# PWM-Power.net
KiCad netlist of a schematic drawn in Altium Designer
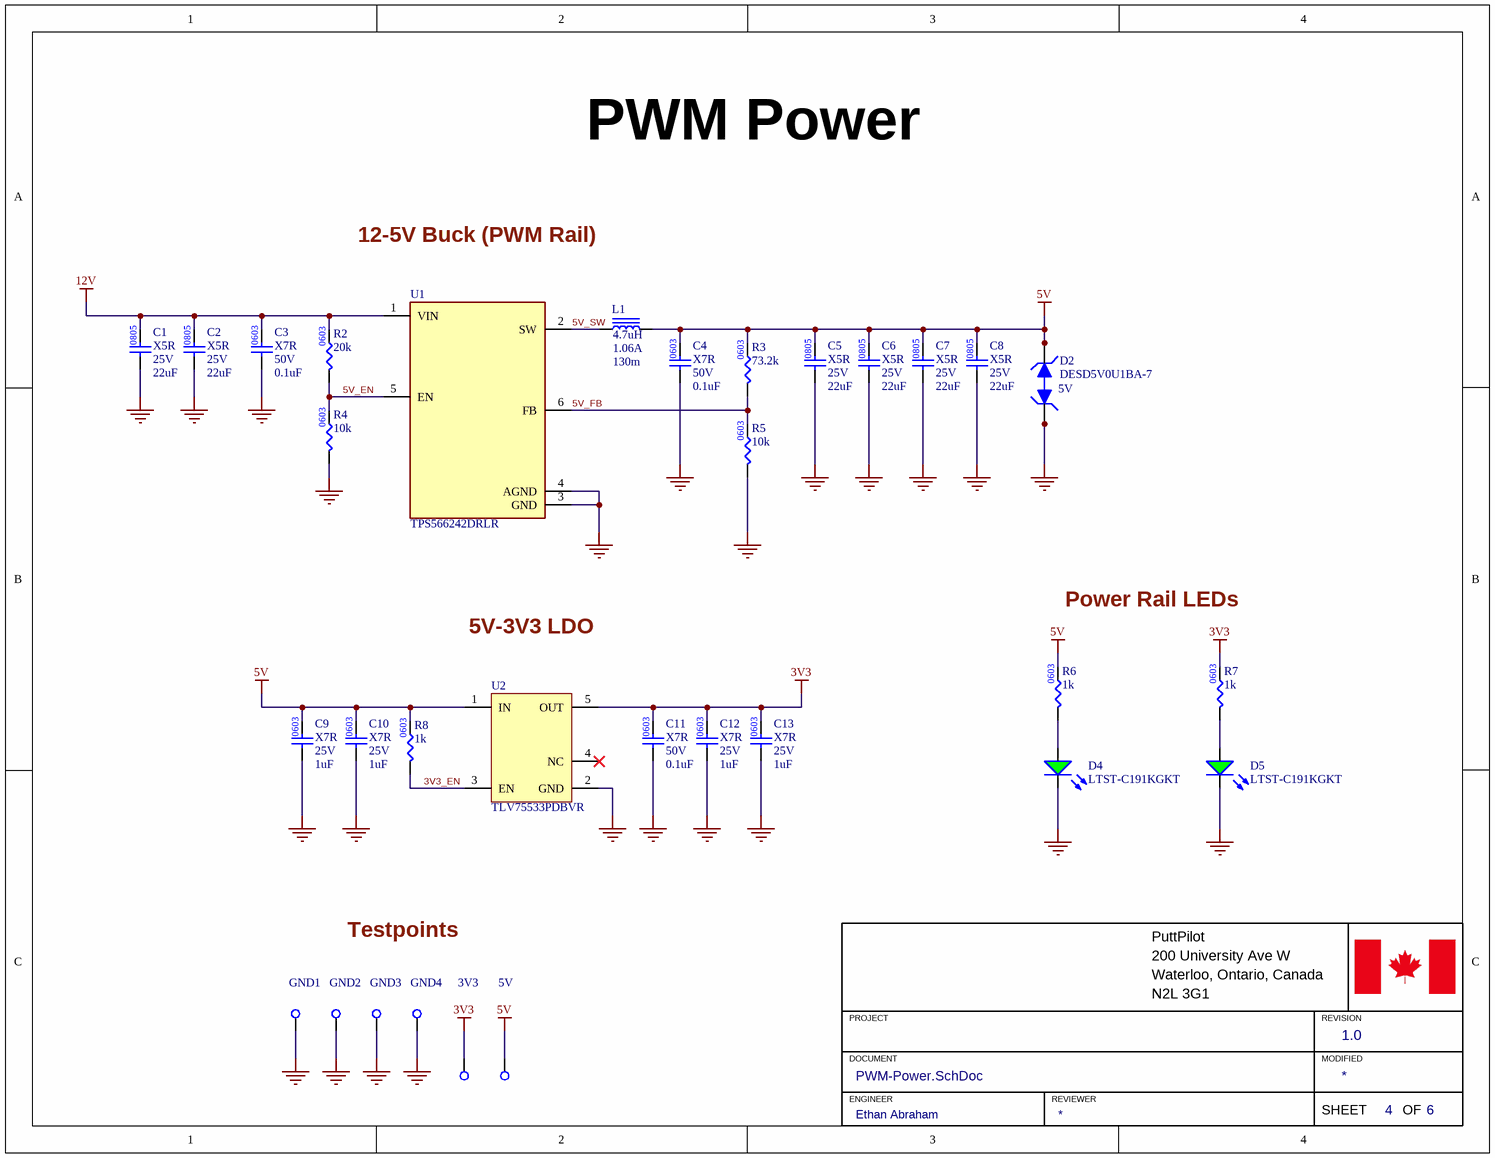
[diagram p0: PWM-Power.SchDoc]

(export (version "E")
  (design (tool "Eeschema 10.0.6"))
  (components
    (comp (ref "3V3")
      (value "RCWCTE")
      (footprint "RCWCTE")
      (description "SMT Test Point")
      (fields (field (name "MANUFACTURER") "KOA Speer"))
      (libsource (lib "PuttPilot") (part "RCWCTE"))
    )
    (comp (ref "5V")
      (value "RCWCTE")
      (footprint "RCWCTE")
      (description "SMT Test Point")
      (fields (field (name "MANUFACTURER") "KOA Speer"))
      (libsource (lib "PuttPilot") (part "RCWCTE"))
    )
    (comp (ref "C1")
      (value "GRM21BR61E226ME44K")
      (footprint ".CAP_0805")
      (description "CAP CER 22uF 25V X5R 0805")
      (fields
        (field (name "MANUFACTURER") "Murata")
        (field (name "TEMPERATURE CHARACTERISTICS CODE") "X5R")
        (field (name "RATED DC VOLTAGE (URDC)") "25V")
        (field (name "CAPACITANCE") "22uF")
      )
      (libsource (lib "PuttPilot") (part "GRM21BR61E226ME44K"))
    )
    (comp (ref "C2")
      (value "GRM21BR61E226ME44K")
      (footprint ".CAP_0805")
      (description "CAP CER 22uF 25V X5R 0805")
      (fields
        (field (name "MANUFACTURER") "Murata")
        (field (name "TEMPERATURE CHARACTERISTICS CODE") "X5R")
        (field (name "RATED DC VOLTAGE (URDC)") "25V")
        (field (name "CAPACITANCE") "22uF")
      )
      (libsource (lib "PuttPilot") (part "GRM21BR61E226ME44K"))
    )
    (comp (ref "C3")
      (value "GCJ188R71H104KA12D")
      (footprint ".CAP_0603")
      (description "CAP CER 0.1uF 50V X7R 0603")
      (fields
        (field (name "MANUFACTURER") "Murata")
        (field (name "TEMPERATURE CHARACTERISTICS CODE") "X7R")
        (field (name "RATED DC VOLTAGE (URDC)") "50V")
        (field (name "CAPACITANCE") "0.1uF")
      )
      (libsource (lib "PuttPilot") (part "GCJ188R71H104KA12D"))
    )
    (comp (ref "C4")
      (value "GCJ188R71H104KA12D")
      (footprint ".CAP_0603")
      (description "CAP CER 0.1uF 50V X7R 0603")
      (fields
        (field (name "MANUFACTURER") "Murata")
        (field (name "TEMPERATURE CHARACTERISTICS CODE") "X7R")
        (field (name "RATED DC VOLTAGE (URDC)") "50V")
        (field (name "CAPACITANCE") "0.1uF")
      )
      (libsource (lib "PuttPilot") (part "GCJ188R71H104KA12D"))
    )
    (comp (ref "C5")
      (value "GRM21BR61E226ME44K")
      (footprint ".CAP_0805")
      (description "CAP CER 22uF 25V X5R 0805")
      (fields
        (field (name "MANUFACTURER") "Murata")
        (field (name "TEMPERATURE CHARACTERISTICS CODE") "X5R")
        (field (name "RATED DC VOLTAGE (URDC)") "25V")
        (field (name "CAPACITANCE") "22uF")
      )
      (libsource (lib "PuttPilot") (part "GRM21BR61E226ME44K"))
    )
    (comp (ref "C6")
      (value "GRM21BR61E226ME44K")
      (footprint ".CAP_0805")
      (description "CAP CER 22uF 25V X5R 0805")
      (fields
        (field (name "MANUFACTURER") "Murata")
        (field (name "TEMPERATURE CHARACTERISTICS CODE") "X5R")
        (field (name "RATED DC VOLTAGE (URDC)") "25V")
        (field (name "CAPACITANCE") "22uF")
      )
      (libsource (lib "PuttPilot") (part "GRM21BR61E226ME44K"))
    )
    (comp (ref "C7")
      (value "GRM21BR61E226ME44K")
      (footprint ".CAP_0805")
      (description "CAP CER 22uF 25V X5R 0805")
      (fields
        (field (name "MANUFACTURER") "Murata")
        (field (name "TEMPERATURE CHARACTERISTICS CODE") "X5R")
        (field (name "RATED DC VOLTAGE (URDC)") "25V")
        (field (name "CAPACITANCE") "22uF")
      )
      (libsource (lib "PuttPilot") (part "GRM21BR61E226ME44K"))
    )
    (comp (ref "C8")
      (value "GRM21BR61E226ME44K")
      (footprint ".CAP_0805")
      (description "CAP CER 22uF 25V X5R 0805")
      (fields
        (field (name "MANUFACTURER") "Murata")
        (field (name "TEMPERATURE CHARACTERISTICS CODE") "X5R")
        (field (name "RATED DC VOLTAGE (URDC)") "25V")
        (field (name "CAPACITANCE") "22uF")
      )
      (libsource (lib "PuttPilot") (part "GRM21BR61E226ME44K"))
    )
    (comp (ref "C9")
      (value "GRT188R71E105KE13D")
      (footprint ".CAP_0603")
      (description "CAP CER 1uF 25V X7R 0603")
      (fields
        (field (name "MANUFACTURER") "Murata")
        (field (name "TEMPERATURE CHARACTERISTICS CODE") "X7R")
        (field (name "RATED DC VOLTAGE (URDC)") "25V")
        (field (name "CAPACITANCE") "1uF")
      )
      (libsource (lib "PuttPilot") (part "GRT188R71E105KE13D"))
    )
    (comp (ref "C10")
      (value "GRT188R71E105KE13D")
      (footprint ".CAP_0603")
      (description "CAP CER 1uF 25V X7R 0603")
      (fields
        (field (name "MANUFACTURER") "Murata")
        (field (name "TEMPERATURE CHARACTERISTICS CODE") "X7R")
        (field (name "RATED DC VOLTAGE (URDC)") "25V")
        (field (name "CAPACITANCE") "1uF")
      )
      (libsource (lib "PuttPilot") (part "GRT188R71E105KE13D"))
    )
    (comp (ref "C11")
      (value "GCJ188R71H104KA12D")
      (footprint ".CAP_0603")
      (description "CAP CER 0.1uF 50V X7R 0603")
      (fields
        (field (name "MANUFACTURER") "Murata")
        (field (name "TEMPERATURE CHARACTERISTICS CODE") "X7R")
        (field (name "RATED DC VOLTAGE (URDC)") "50V")
        (field (name "CAPACITANCE") "0.1uF")
      )
      (libsource (lib "PuttPilot") (part "GCJ188R71H104KA12D"))
    )
    (comp (ref "C12")
      (value "GRT188R71E105KE13D")
      (footprint ".CAP_0603")
      (description "CAP CER 1uF 25V X7R 0603")
      (fields
        (field (name "MANUFACTURER") "Murata")
        (field (name "TEMPERATURE CHARACTERISTICS CODE") "X7R")
        (field (name "RATED DC VOLTAGE (URDC)") "25V")
        (field (name "CAPACITANCE") "1uF")
      )
      (libsource (lib "PuttPilot") (part "GRT188R71E105KE13D"))
    )
    (comp (ref "C13")
      (value "GRT188R71E105KE13D")
      (footprint ".CAP_0603")
      (description "CAP CER 1uF 25V X7R 0603")
      (fields
        (field (name "MANUFACTURER") "Murata")
        (field (name "TEMPERATURE CHARACTERISTICS CODE") "X7R")
        (field (name "RATED DC VOLTAGE (URDC)") "25V")
        (field (name "CAPACITANCE") "1uF")
      )
      (libsource (lib "PuttPilot") (part "GRT188R71E105KE13D"))
    )
    (comp (ref "D2")
      (value "DESD5V0U1BA-7")
      (footprint "DESD5V0U1BA-7")
      (description "TVS DIODE 5VWM")
      (fields (field (name "MANUFACTURER") "Diodes") (field (name "REP PK REVERSE VOLTAGE-MAX") "5V"))
      (libsource (lib "PuttPilot") (part "DESD5V0U1BA-7"))
    )
    (comp (ref "D4")
      (value "LTST-C191KGKT")
      (footprint ".LED_0603")
      (description "LED GREEN 2V 0603")
      (fields (field (name "MANUFACTURER") "Vishay Lite-On"))
      (libsource (lib "PuttPilot") (part "LTST-C191KGKT"))
    )
    (comp (ref "D5")
      (value "LTST-C191KGKT")
      (footprint ".LED_0603")
      (description "LED GREEN 2V 0603")
      (fields (field (name "MANUFACTURER") "Vishay Lite-On"))
      (libsource (lib "PuttPilot") (part "LTST-C191KGKT"))
    )
    (comp (ref "GND1")
      (value "RCWCTE")
      (footprint "RCWCTE")
      (description "SMT Test Point")
      (fields (field (name "MANUFACTURER") "KOA Speer"))
      (libsource (lib "PuttPilot") (part "RCWCTE"))
    )
    (comp (ref "GND2")
      (value "RCWCTE")
      (footprint "RCWCTE")
      (description "SMT Test Point")
      (fields (field (name "MANUFACTURER") "KOA Speer"))
      (libsource (lib "PuttPilot") (part "RCWCTE"))
    )
    (comp (ref "GND3")
      (value "RCWCTE")
      (footprint "RCWCTE")
      (description "SMT Test Point")
      (fields (field (name "MANUFACTURER") "KOA Speer"))
      (libsource (lib "PuttPilot") (part "RCWCTE"))
    )
    (comp (ref "GND4")
      (value "RCWCTE")
      (footprint "RCWCTE")
      (description "SMT Test Point")
      (fields (field (name "MANUFACTURER") "KOA Speer"))
      (libsource (lib "PuttPilot") (part "RCWCTE"))
    )
    (comp (ref "L1")
      (value "NRH3012T4R7MN")
      (footprint "NRH3012T4R7MN")
      (description "FIXED IND 4.7uH 1.06A")
      (fields
        (field (name "MANUFACTURER") "Taiyo Yuden")
        (field (name "TOLERANCE") "20%")
        (field (name "DC RESISTANCE (DCR)") "130m")
        (field (name "INDUCTANCE-NOM (L)") "4.7uH")
        (field (name "RATED CURRENT-MAX") "1.06A")
      )
      (libsource (lib "PuttPilot") (part "NRH3012T4R7MN"))
    )
    (comp (ref "R2")
      (value "ERJ-3EKF2002V")
      (footprint ".RES_0603")
      (description "RES 20K OHM 0603")
      (fields
        (field (name "MANUFACTURER") "Panasonic")
        (field (name "TOLERANCE") "1%")
        (field (name "RESISTANCE") "20k")
      )
      (libsource (lib "PuttPilot") (part "ERJ-3EKF2002V"))
    )
    (comp (ref "R3")
      (value "RC0603FR-0773K2L")
      (footprint ".RES_0603")
      (description "RES 73.2K OHM 0603")
      (fields
        (field (name "MANUFACTURER") "Yageo")
        (field (name "TOLERANCE") "1%")
        (field (name "RESISTANCE") "73.2k")
      )
      (libsource (lib "PuttPilot") (part "RC0603FR-0773K2L"))
    )
    (comp (ref "R4")
      (value "RC0603FR-0710KL")
      (footprint ".RES_0603")
      (description "RES 10K OHM 0603")
      (fields
        (field (name "MANUFACTURER") "Yageo")
        (field (name "TOLERANCE") "1%")
        (field (name "RESISTANCE") "10k")
      )
      (libsource (lib "PuttPilot") (part "RC0603FR-0710KL"))
    )
    (comp (ref "R5")
      (value "RC0603FR-0710KL")
      (footprint ".RES_0603")
      (description "RES 10K OHM 0603")
      (fields
        (field (name "MANUFACTURER") "Yageo")
        (field (name "TOLERANCE") "1%")
        (field (name "RESISTANCE") "10k")
      )
      (libsource (lib "PuttPilot") (part "RC0603FR-0710KL"))
    )
    (comp (ref "R6")
      (value "RC0603FR-071KL")
      (footprint ".RES_0603")
      (description "RES 1K OHM 0603")
      (fields
        (field (name "MANUFACTURER") "Yageo")
        (field (name "TOLERANCE") "1%")
        (field (name "RESISTANCE") "1k")
      )
      (libsource (lib "PuttPilot") (part "RC0603FR-071KL"))
    )
    (comp (ref "R7")
      (value "RC0603FR-071KL")
      (footprint ".RES_0603")
      (description "RES 1K OHM 0603")
      (fields
        (field (name "MANUFACTURER") "Yageo")
        (field (name "TOLERANCE") "1%")
        (field (name "RESISTANCE") "1k")
      )
      (libsource (lib "PuttPilot") (part "RC0603FR-071KL"))
    )
    (comp (ref "R8")
      (value "RC0603FR-071KL")
      (footprint ".RES_0603")
      (description "RES 1K OHM 0603")
      (fields
        (field (name "MANUFACTURER") "Yageo")
        (field (name "TOLERANCE") "1%")
        (field (name "RESISTANCE") "1k")
      )
      (libsource (lib "PuttPilot") (part "RC0603FR-071KL"))
    )
    (comp (ref "U1")
      (value "TPS566242DRLR")
      (footprint "TPS566242DRLR")
      (description "BUCK 3V-16V 6A SOT-563")
      (fields (field (name "MANUFACTURER") "Texas Instruments"))
      (libsource (lib "PuttPilot") (part "TPS566242DRLR"))
    )
    (comp (ref "U2")
      (value "TLV75533PDBVR")
      (footprint ".SOT-23-5")
      (description "3V3 (Fixed) LDO 500mA SOT25")
      (fields (field (name "MANUFACTURER") "Texas Instruments"))
      (libsource (lib "PuttPilot") (part "TLV75533PDBVR"))
    )
  )
  (nets
    (net (code "1") (name "/3V3_EN") (class "Default")
      (node (ref "R8") (pin "1") (pinfunction "1_1") (pintype "passive"))
      (node (ref "U2") (pin "3") (pinfunction "EN_3") (pintype "passive"))
    )
    (net (code "2") (name "/5V_EN") (class "Default")
      (node (ref "R2") (pin "1") (pinfunction "1_1") (pintype "passive"))
      (node (ref "R4") (pin "2") (pinfunction "2_2") (pintype "passive"))
      (node (ref "U1") (pin "5") (pinfunction "EN_5") (pintype "passive"))
    )
    (net (code "3") (name "/5V_FB") (class "Default")
      (node (ref "R3") (pin "1") (pinfunction "1_1") (pintype "passive"))
      (node (ref "R5") (pin "2") (pinfunction "2_2") (pintype "passive"))
      (node (ref "U1") (pin "6") (pinfunction "FB_6") (pintype "passive"))
    )
    (net (code "4") (name "/5V_SW") (class "Default")
      (node (ref "L1") (pin "1") (pinfunction "1_1") (pintype "passive"))
      (node (ref "U1") (pin "2") (pinfunction "SW_2") (pintype "passive"))
    )
    (net (code "5") (name "3V3") (class "Default")
      (node (ref "3V3") (pin "1") (pinfunction "1_1") (pintype "passive"))
      (node (ref "C11") (pin "2") (pinfunction "2_2") (pintype "passive"))
      (node (ref "C12") (pin "2") (pinfunction "2_2") (pintype "passive"))
      (node (ref "C13") (pin "2") (pinfunction "2_2") (pintype "passive"))
      (node (ref "R7") (pin "2") (pinfunction "2_2") (pintype "passive"))
      (node (ref "U2") (pin "5") (pinfunction "OUT_5") (pintype "passive"))
    )
    (net (code "6") (name "5V") (class "Default")
      (node (ref "5V") (pin "1") (pinfunction "1_1") (pintype "passive"))
      (node (ref "C10") (pin "2") (pinfunction "2_2") (pintype "passive"))
      (node (ref "C4") (pin "2") (pinfunction "2_2") (pintype "passive"))
      (node (ref "C5") (pin "2") (pinfunction "2_2") (pintype "passive"))
      (node (ref "C6") (pin "2") (pinfunction "2_2") (pintype "passive"))
      (node (ref "C7") (pin "2") (pinfunction "2_2") (pintype "passive"))
      (node (ref "C8") (pin "2") (pinfunction "2_2") (pintype "passive"))
      (node (ref "C9") (pin "2") (pinfunction "2_2") (pintype "passive"))
      (node (ref "D2") (pin "2") (pinfunction "Pin_2_2") (pintype "passive"))
      (node (ref "L1") (pin "2") (pinfunction "2_2") (pintype "passive"))
      (node (ref "R3") (pin "2") (pinfunction "2_2") (pintype "passive"))
      (node (ref "R6") (pin "2") (pinfunction "2_2") (pintype "passive"))
      (node (ref "R8") (pin "2") (pinfunction "2_2") (pintype "passive"))
      (node (ref "U2") (pin "1") (pinfunction "IN_1") (pintype "passive"))
    )
    (net (code "7") (name "12V") (class "Default")
      (node (ref "C1") (pin "2") (pinfunction "2_2") (pintype "passive"))
      (node (ref "C2") (pin "2") (pinfunction "2_2") (pintype "passive"))
      (node (ref "C3") (pin "2") (pinfunction "2_2") (pintype "passive"))
      (node (ref "R2") (pin "2") (pinfunction "2_2") (pintype "passive"))
      (node (ref "U1") (pin "1") (pinfunction "VIN_1") (pintype "passive"))
    )
    (net (code "8") (name "GND") (class "Default")
      (node (ref "C1") (pin "1") (pinfunction "1_1") (pintype "passive"))
      (node (ref "C10") (pin "1") (pinfunction "1_1") (pintype "passive"))
      (node (ref "C11") (pin "1") (pinfunction "1_1") (pintype "passive"))
      (node (ref "C12") (pin "1") (pinfunction "1_1") (pintype "passive"))
      (node (ref "C13") (pin "1") (pinfunction "1_1") (pintype "passive"))
      (node (ref "C2") (pin "1") (pinfunction "1_1") (pintype "passive"))
      (node (ref "C3") (pin "1") (pinfunction "1_1") (pintype "passive"))
      (node (ref "C4") (pin "1") (pinfunction "1_1") (pintype "passive"))
      (node (ref "C5") (pin "1") (pinfunction "1_1") (pintype "passive"))
      (node (ref "C6") (pin "1") (pinfunction "1_1") (pintype "passive"))
      (node (ref "C7") (pin "1") (pinfunction "1_1") (pintype "passive"))
      (node (ref "C8") (pin "1") (pinfunction "1_1") (pintype "passive"))
      (node (ref "C9") (pin "1") (pinfunction "1_1") (pintype "passive"))
      (node (ref "D2") (pin "1") (pinfunction "Pin_1_1") (pintype "passive"))
      (node (ref "D4") (pin "2") (pinfunction "K_2") (pintype "passive"))
      (node (ref "D5") (pin "2") (pinfunction "K_2") (pintype "passive"))
      (node (ref "GND1") (pin "1") (pinfunction "1_1") (pintype "passive"))
      (node (ref "GND2") (pin "1") (pinfunction "1_1") (pintype "passive"))
      (node (ref "GND3") (pin "1") (pinfunction "1_1") (pintype "passive"))
      (node (ref "GND4") (pin "1") (pinfunction "1_1") (pintype "passive"))
      (node (ref "R4") (pin "1") (pinfunction "1_1") (pintype "passive"))
      (node (ref "R5") (pin "1") (pinfunction "1_1") (pintype "passive"))
      (node (ref "U1") (pin "3") (pinfunction "GND_3") (pintype "passive"))
      (node (ref "U1") (pin "4") (pinfunction "AGND_4") (pintype "passive"))
      (node (ref "U2") (pin "2") (pinfunction "GND_2") (pintype "passive"))
    )
    (net (code "9") (name "Net-(D4-A)") (class "Default")
      (node (ref "D4") (pin "1") (pinfunction "A_1") (pintype "passive"))
      (node (ref "R6") (pin "1") (pinfunction "1_1") (pintype "passive"))
    )
    (net (code "10") (name "Net-(D5-A)") (class "Default")
      (node (ref "D5") (pin "1") (pinfunction "A_1") (pintype "passive"))
      (node (ref "R7") (pin "1") (pinfunction "1_1") (pintype "passive"))
    )
    (net (code "11") (name "unconnected-(U2-NC-Pad4)") (class "Default")
      (node (ref "U2") (pin "4") (pinfunction "NC_4") (pintype "passive+no_connect"))
    )
  )
)
